# Node_MCU_Schematics_I2C_Pinout_v3_02_202.net
KiCad netlist of a schematic drawn in Altium Designer
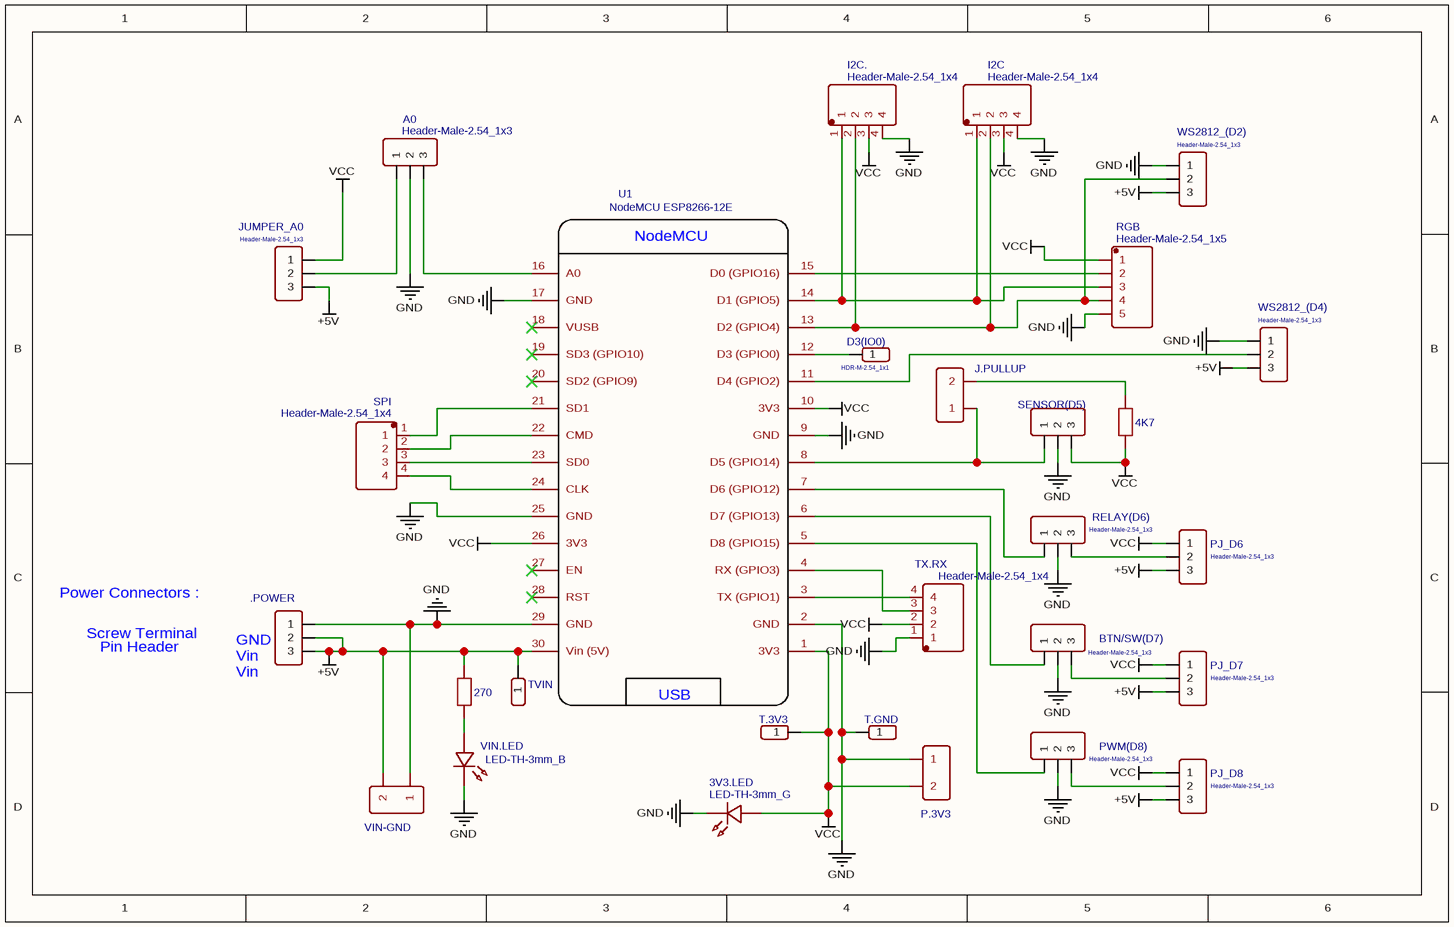
[diagram p0: Node MCU_Schematics I2C Pinout v3.02_2022-01-05.schdoc]

(export (version "E")
  (design (tool "Eeschema 10.0.6"))
  (components
    (comp (ref ".POWER")
      (value "Header-Male-2.54_1x3")
      (fields
        (field (name "BOM_MANUFACTURER PART") "Header2.54mm 1*3P")
        (field (name "BOM_SUPPLIER PART") "C49257")
      )
      (libsource (lib "altium-import") (part "root_2_Header-Male-2.54_1x3_"))
    )
    (comp (ref "3V3.LED")
      (value "LED-TH-3mm_G")
      (fields
        (field (name "BOM_MANUFACTURER PART") "204-10SYGD/S530-E3")
        (field (name "BOM_SUPPLIER PART") "C85161")
        (field (name "CONTRIBUTOR") "LCEDA_Lib")
      )
      (libsource (lib "altium-import") (part "root_2_LED-TH-3mm_G_"))
    )
    (comp (ref "4K7") (value "4k7") (libsource (lib "altium-import") (part "root_1_4k7_")))
    (comp (ref "270") (value "4k7") (libsource (lib "altium-import") (part "root_1_4k7_")))
    (comp (ref "A0")
      (value "Header-Male-2.54_1x3")
      (fields
        (field (name "BOM_MANUFACTURER PART") "Header2.54mm 1*3P")
        (field (name "BOM_SUPPLIER PART") "C49257")
      )
      (libsource (lib "altium-import") (part "root_1_Header-Male-2.54_1x3_"))
    )
    (comp (ref "BTN/SW(D7)")
      (value "Header-Male-2.54_1x3")
      (fields
        (field (name "BOM_MANUFACTURER PART") "Header2.54mm 1*3P")
        (field (name "BOM_SUPPLIER PART") "C49257")
      )
      (libsource (lib "altium-import") (part "root_1_Header-Male-2.54_1x3_"))
    )
    (comp (ref "D3(IO0)")
      (value "HDR-M-2.54_1x1")
      (fields (field (name "BOM_SUPPLIER PART") "C81276") (field (name "CONTRIBUTOR") "LCEDA_Lib"))
      (libsource (lib "altium-import") (part "root_0_HDR-M-2.54_1x1_"))
    )
    (comp (ref "I2C")
      (value "Header-Male-2.54_1x4")
      (fields
        (field (name "BOM_MANUFACTURER PART") "210S-1*4P L=11.6MMGold-plated black")
        (field (name "BOM_SUPPLIER PART") "C124378")
        (field (name "CONTRIBUTOR") "LCSC")
      )
      (libsource (lib "altium-import") (part "root_1_Header-Male-2.54_1x4_"))
    )
    (comp (ref "I2C.")
      (value "Header-Male-2.54_1x4")
      (fields
        (field (name "BOM_MANUFACTURER PART") "210S-1*4P L=11.6MMGold-plated black")
        (field (name "BOM_SUPPLIER PART") "C124378")
        (field (name "CONTRIBUTOR") "LCSC")
      )
      (libsource (lib "altium-import") (part "root_1_Header-Male-2.54_1x4_"))
    )
    (comp (ref "J.PULLUP")
      (value "Header-Male-2.54_1x2")
      (fields (field (name "BOM_MANUFACTURER PART") "826629-2") (field (name "BOM_SUPPLIER PART") "C86471"))
      (libsource (lib "altium-import") (part "root_2_Header-Male-2.54_1x2_"))
    )
    (comp (ref "JUMPER_A0")
      (value "Header-Male-2.54_1x3")
      (fields
        (field (name "BOM_MANUFACTURER PART") "Header2.54mm 1*3P")
        (field (name "BOM_SUPPLIER PART") "C49257")
      )
      (libsource (lib "altium-import") (part "root_0_Header-Male-2.54_1x3_"))
    )
    (comp (ref "P.3V3")
      (value "Header-Male-2.54_1x2")
      (fields (field (name "BOM_MANUFACTURER PART") "826629-2") (field (name "BOM_SUPPLIER PART") "C86471"))
      (libsource (lib "altium-import") (part "root_0_Header-Male-2.54_1x2_"))
    )
    (comp (ref "PJ_D6")
      (value "Header-Male-2.54_1x3")
      (fields
        (field (name "BOM_MANUFACTURER PART") "Header2.54mm 1*3P")
        (field (name "BOM_SUPPLIER PART") "C49257")
      )
      (libsource (lib "") (part "root_0_Header-Male-2.54_1x3__1"))
    )
    (comp (ref "PJ_D7")
      (value "Header-Male-2.54_1x3")
      (fields
        (field (name "BOM_MANUFACTURER PART") "Header2.54mm 1*3P")
        (field (name "BOM_SUPPLIER PART") "C49257")
      )
      (libsource (lib "") (part "root_0_Header-Male-2.54_1x3__1"))
    )
    (comp (ref "PJ_D8")
      (value "Header-Male-2.54_1x3")
      (fields
        (field (name "BOM_MANUFACTURER PART") "Header2.54mm 1*3P")
        (field (name "BOM_SUPPLIER PART") "C49257")
      )
      (libsource (lib "") (part "root_0_Header-Male-2.54_1x3__1"))
    )
    (comp (ref "PWM(D8)")
      (value "Header-Male-2.54_1x3")
      (fields
        (field (name "BOM_MANUFACTURER PART") "Header2.54mm 1*3P")
        (field (name "BOM_SUPPLIER PART") "C49257")
      )
      (libsource (lib "altium-import") (part "root_1_Header-Male-2.54_1x3_"))
    )
    (comp (ref "RELAY(D6)")
      (value "Header-Male-2.54_1x3")
      (fields
        (field (name "BOM_MANUFACTURER PART") "Header2.54mm 1*3P")
        (field (name "BOM_SUPPLIER PART") "C49257")
      )
      (libsource (lib "altium-import") (part "root_1_Header-Male-2.54_1x3_"))
    )
    (comp (ref "RGB")
      (value "Header-Male-2.54_1x5")
      (fields
        (field (name "BOM_MANUFACTURER PART") "210S-1*5P L=11.6MMGold-plated black")
        (field (name "BOM_SUPPLIER PART") "C124379")
        (field (name "CONTRIBUTOR") "LCSC")
      )
      (libsource (lib "altium-import") (part "root_0_Header-Male-2.54_1x5_"))
    )
    (comp (ref "SENSOR(D5)")
      (value "Header-Male-2.54_1x3")
      (fields
        (field (name "BOM_MANUFACTURER PART") "Header2.54mm 1*3P")
        (field (name "BOM_SUPPLIER PART") "C49257")
      )
      (libsource (lib "altium-import") (part "root_1_Header-Male-2.54_1x3_"))
    )
    (comp (ref "SPI")
      (value "Header-Male-2.54_1x4")
      (fields
        (field (name "BOM_MANUFACTURER PART") "210S-1*4P L=11.6MMGold-plated black")
        (field (name "BOM_SUPPLIER PART") "C124378")
        (field (name "CONTRIBUTOR") "LCSC")
      )
      (libsource (lib "altium-import") (part "root_0_Header-Male-2.54_1x4_"))
    )
    (comp (ref "T.3V3")
      (value "Header-Male-2.54_1x1")
      (fields (field (name "BOM_SUPPLIER PART") "C81276"))
      (libsource (lib "altium-import") (part "root_2_Header-Male-2.54_1x1_"))
    )
    (comp (ref "T.GND")
      (value "Header-Male-2.54_1x1")
      (fields (field (name "BOM_SUPPLIER PART") "C81276"))
      (libsource (lib "altium-import") (part "root_0_Header-Male-2.54_1x1_"))
    )
    (comp (ref "TVIN")
      (value "TVin")
      (fields
        (field (name "BOM_MANUFACTURER PART") "Header-Male-2.54_1x1")
        (field (name "BOM_SUPPLIER PART") "C81276")
      )
      (libsource (lib "altium-import") (part "root_3_TVin_"))
    )
    (comp (ref "TX.RX")
      (value "Header-Male-2.54_1x4")
      (fields
        (field (name "BOM_MANUFACTURER PART") "210S-1*4P L=11.6MMGold-plated black")
        (field (name "BOM_SUPPLIER PART") "C124378")
        (field (name "CONTRIBUTOR") "LCSC")
      )
      (libsource (lib "altium-import") (part "root_2_Header-Male-2.54_1x4_"))
    )
    (comp (ref "U1")
      (value "NodeMCU ESP8266-12E")
      (fields
        (field (name "BOM_MANUFACTURER PART") "?")
        (field (name "BOM_SUPPLIER PART") "nodemcu-v2")
        (field (name "CONTRIBUTOR") "irukard")
        (field (name "AUTHOR") "Krzysztof Daszuta")
      )
      (libsource (lib "altium-import") (part "root_2_NodeMCU ESP8266-12E_"))
    )
    (comp (ref "VIN-GND")
      (value "Header-Male-2.54_1x2")
      (fields (field (name "BOM_MANUFACTURER PART") "826629-2") (field (name "BOM_SUPPLIER PART") "C86471"))
      (libsource (lib "altium-import") (part "root_3_Header-Male-2.54_1x2_"))
    )
    (comp (ref "VIN.LED")
      (value "LED-TH-3mm_B")
      (fields
        (field (name "BOM_MANUFACTURER PART") "204-10SUBC/S400-A4")
        (field (name "BOM_SUPPLIER PART") "C86881")
        (field (name "CONTRIBUTOR") "LCEDA_Lib")
      )
      (libsource (lib "altium-import") (part "root_3_LED-TH-3mm_B_"))
    )
    (comp (ref "WS2812_(D2)")
      (value "Header-Male-2.54_1x3")
      (fields
        (field (name "BOM_MANUFACTURER PART") "Header2.54mm 1*3P")
        (field (name "BOM_SUPPLIER PART") "C49257")
      )
      (libsource (lib "") (part "root_0_Header-Male-2.54_1x3__1"))
    )
    (comp (ref "WS2812_(D4)")
      (value "Header-Male-2.54_1x3")
      (fields
        (field (name "BOM_MANUFACTURER PART") "Header2.54mm 1*3P")
        (field (name "BOM_SUPPLIER PART") "C49257")
      )
      (libsource (lib "") (part "root_0_Header-Male-2.54_1x3__1"))
    )
  )
  (nets
    (net (code "1") (name "+5V") (class "Default")
      (node (ref ".POWER") (pin "2") (pinfunction "2_2") (pintype "passive"))
      (node (ref ".POWER") (pin "3") (pinfunction "3_3") (pintype "passive"))
      (node (ref "270") (pin "2") (pinfunction "2_2") (pintype "passive"))
      (node (ref "JUMPER_A0") (pin "3") (pinfunction "3_3") (pintype "passive"))
      (node (ref "PJ_D6") (pin "3") (pinfunction "3_3") (pintype "passive"))
      (node (ref "PJ_D7") (pin "3") (pinfunction "3_3") (pintype "passive"))
      (node (ref "PJ_D8") (pin "3") (pinfunction "3_3") (pintype "passive"))
      (node (ref "TVIN") (pin "1") (pinfunction "1_1") (pintype "passive"))
      (node (ref "U1") (pin "30") (pinfunction "Vin_(5V)_30") (pintype "passive"))
      (node (ref "VIN-GND") (pin "2") (pinfunction "2_2") (pintype "passive"))
      (node (ref "WS2812_(D2)") (pin "3") (pinfunction "3_3") (pintype "passive"))
      (node (ref "WS2812_(D4)") (pin "3") (pinfunction "3_3") (pintype "passive"))
    )
    (net (code "2") (name "GND") (class "Default")
      (node (ref ".POWER") (pin "1") (pinfunction "1_1") (pintype "passive"))
      (node (ref "3V3.LED") (pin "2") (pinfunction "2_2") (pintype "passive"))
      (node (ref "A0") (pin "2") (pinfunction "2_2") (pintype "passive"))
      (node (ref "BTN/SW(D7)") (pin "2") (pinfunction "2_2") (pintype "passive"))
      (node (ref "I2C") (pin "4") (pinfunction "4_4") (pintype "passive"))
      (node (ref "I2C.") (pin "4") (pinfunction "4_4") (pintype "passive"))
      (node (ref "P.3V3") (pin "1") (pinfunction "1_1") (pintype "passive"))
      (node (ref "PWM(D8)") (pin "2") (pinfunction "2_2") (pintype "passive"))
      (node (ref "RELAY(D6)") (pin "2") (pinfunction "2_2") (pintype "passive"))
      (node (ref "RGB") (pin "5") (pinfunction "5_5") (pintype "passive"))
      (node (ref "SENSOR(D5)") (pin "2") (pinfunction "2_2") (pintype "passive"))
      (node (ref "T.GND") (pin "1") (pinfunction "1_1") (pintype "passive"))
      (node (ref "TX.RX") (pin "1") (pinfunction "1_1") (pintype "passive"))
      (node (ref "U1") (pin "17") (pinfunction "GND_17") (pintype "passive"))
      (node (ref "U1") (pin "2") (pinfunction "GND_2") (pintype "passive"))
      (node (ref "U1") (pin "25") (pinfunction "GND_25") (pintype "passive"))
      (node (ref "U1") (pin "29") (pinfunction "GND_29") (pintype "passive"))
      (node (ref "U1") (pin "9") (pinfunction "GND_9") (pintype "passive"))
      (node (ref "VIN-GND") (pin "1") (pinfunction "1_1") (pintype "passive"))
      (node (ref "VIN.LED") (pin "2") (pinfunction "2_2") (pintype "passive"))
      (node (ref "WS2812_(D2)") (pin "1") (pinfunction "1_1") (pintype "passive"))
      (node (ref "WS2812_(D4)") (pin "1") (pinfunction "1_1") (pintype "passive"))
    )
    (net (code "3") (name "Net-(4K7-Pad2)") (class "Default")
      (node (ref "4K7") (pin "2") (pinfunction "2_2") (pintype "passive"))
      (node (ref "J.PULLUP") (pin "2") (pinfunction "2_2") (pintype "passive"))
    )
    (net (code "4") (name "Net-(270-Pad1)") (class "Default")
      (node (ref "270") (pin "1") (pinfunction "1_1") (pintype "passive"))
      (node (ref "VIN.LED") (pin "1") (pinfunction "1_1") (pintype "passive"))
    )
    (net (code "5") (name "Net-(A0-Pad1)") (class "Default")
      (node (ref "A0") (pin "1") (pinfunction "1_1") (pintype "passive"))
      (node (ref "JUMPER_A0") (pin "2") (pinfunction "2_2") (pintype "passive"))
    )
    (net (code "6") (name "Net-(BTN/SW(D7)-Pad3)") (class "Default")
      (node (ref "BTN/SW(D7)") (pin "3") (pinfunction "3_3") (pintype "passive"))
      (node (ref "PJ_D7") (pin "2") (pinfunction "2_2") (pintype "passive"))
    )
    (net (code "7") (name "Net-(PJ_D6-Pad2)") (class "Default")
      (node (ref "PJ_D6") (pin "2") (pinfunction "2_2") (pintype "passive"))
      (node (ref "RELAY(D6)") (pin "3") (pinfunction "3_3") (pintype "passive"))
    )
    (net (code "8") (name "Net-(PJ_D8-Pad2)") (class "Default")
      (node (ref "PJ_D8") (pin "2") (pinfunction "2_2") (pintype "passive"))
      (node (ref "PWM(D8)") (pin "3") (pinfunction "3_3") (pintype "passive"))
    )
    (net (code "9") (name "Net-(U1-A0)") (class "Default")
      (node (ref "A0") (pin "3") (pinfunction "3_3") (pintype "passive"))
      (node (ref "U1") (pin "16") (pinfunction "A0_16") (pintype "passive"))
    )
    (net (code "10") (name "Net-(U1-CLK)") (class "Default")
      (node (ref "SPI") (pin "4") (pinfunction "4_4") (pintype "passive"))
      (node (ref "U1") (pin "24") (pinfunction "CLK_24") (pintype "passive"))
    )
    (net (code "11") (name "Net-(U1-CMD)") (class "Default")
      (node (ref "SPI") (pin "2") (pinfunction "2_2") (pintype "passive"))
      (node (ref "U1") (pin "22") (pinfunction "CMD_22") (pintype "passive"))
    )
    (net (code "12") (name "Net-(U1-D0_(GPIO16))") (class "Default")
      (node (ref "RGB") (pin "2") (pinfunction "2_2") (pintype "passive"))
      (node (ref "U1") (pin "15") (pinfunction "D0_(GPIO16)_15") (pintype "passive"))
    )
    (net (code "13") (name "Net-(U1-D1_(GPIO5))") (class "Default")
      (node (ref "I2C") (pin "1") (pinfunction "1_1") (pintype "passive"))
      (node (ref "I2C.") (pin "1") (pinfunction "1_1") (pintype "passive"))
      (node (ref "RGB") (pin "3") (pinfunction "3_3") (pintype "passive"))
      (node (ref "U1") (pin "14") (pinfunction "D1_(GPIO5)_14") (pintype "passive"))
    )
    (net (code "14") (name "Net-(U1-D2_(GPIO4))") (class "Default")
      (node (ref "I2C") (pin "2") (pinfunction "2_2") (pintype "passive"))
      (node (ref "I2C.") (pin "2") (pinfunction "2_2") (pintype "passive"))
      (node (ref "RGB") (pin "4") (pinfunction "4_4") (pintype "passive"))
      (node (ref "U1") (pin "13") (pinfunction "D2_(GPIO4)_13") (pintype "passive"))
      (node (ref "WS2812_(D2)") (pin "2") (pinfunction "2_2") (pintype "passive"))
    )
    (net (code "15") (name "Net-(U1-D3_(GPIO0))") (class "Default")
      (node (ref "D3(IO0)") (pin "1") (pinfunction "1_1") (pintype "passive"))
      (node (ref "U1") (pin "12") (pinfunction "D3_(GPIO0)_12") (pintype "passive"))
    )
    (net (code "16") (name "Net-(U1-D4_(GPIO2))") (class "Default")
      (node (ref "U1") (pin "11") (pinfunction "D4_(GPIO2)_11") (pintype "passive"))
      (node (ref "WS2812_(D4)") (pin "2") (pinfunction "2_2") (pintype "passive"))
    )
    (net (code "17") (name "Net-(U1-D5_(GPIO14))") (class "Default")
      (node (ref "J.PULLUP") (pin "1") (pinfunction "1_1") (pintype "passive"))
      (node (ref "SENSOR(D5)") (pin "1") (pinfunction "1_1") (pintype "passive"))
      (node (ref "U1") (pin "8") (pinfunction "D5_(GPIO14)_8") (pintype "passive"))
    )
    (net (code "18") (name "Net-(U1-D6_(GPIO12))") (class "Default")
      (node (ref "RELAY(D6)") (pin "1") (pinfunction "1_1") (pintype "passive"))
      (node (ref "U1") (pin "7") (pinfunction "D6_(GPIO12)_7") (pintype "passive"))
    )
    (net (code "19") (name "Net-(U1-D7_(GPIO13))") (class "Default")
      (node (ref "BTN/SW(D7)") (pin "1") (pinfunction "1_1") (pintype "passive"))
      (node (ref "U1") (pin "6") (pinfunction "D7_(GPIO13)_6") (pintype "passive"))
    )
    (net (code "20") (name "Net-(U1-D8_(GPIO15))") (class "Default")
      (node (ref "PWM(D8)") (pin "1") (pinfunction "1_1") (pintype "passive"))
      (node (ref "U1") (pin "5") (pinfunction "D8_(GPIO15)_5") (pintype "passive"))
    )
    (net (code "21") (name "Net-(U1-RX_(GPIO3))") (class "Default")
      (node (ref "TX.RX") (pin "3") (pinfunction "3_3") (pintype "passive"))
      (node (ref "U1") (pin "4") (pinfunction "RX_(GPIO3)_4") (pintype "passive"))
    )
    (net (code "22") (name "Net-(U1-SD0)") (class "Default")
      (node (ref "SPI") (pin "3") (pinfunction "3_3") (pintype "passive"))
      (node (ref "U1") (pin "23") (pinfunction "SD0_23") (pintype "passive"))
    )
    (net (code "23") (name "Net-(U1-SD1)") (class "Default")
      (node (ref "SPI") (pin "1") (pinfunction "1_1") (pintype "passive"))
      (node (ref "U1") (pin "21") (pinfunction "SD1_21") (pintype "passive"))
    )
    (net (code "24") (name "Net-(U1-TX_(GPIO1))") (class "Default")
      (node (ref "TX.RX") (pin "4") (pinfunction "4_4") (pintype "passive"))
      (node (ref "U1") (pin "3") (pinfunction "TX_(GPIO1)_3") (pintype "passive"))
    )
    (net (code "25") (name "VCC") (class "Default")
      (node (ref "3V3.LED") (pin "1") (pinfunction "1_1") (pintype "passive"))
      (node (ref "4K7") (pin "1") (pinfunction "1_1") (pintype "passive"))
      (node (ref "I2C") (pin "3") (pinfunction "3_3") (pintype "passive"))
      (node (ref "I2C.") (pin "3") (pinfunction "3_3") (pintype "passive"))
      (node (ref "JUMPER_A0") (pin "1") (pinfunction "1_1") (pintype "passive"))
      (node (ref "P.3V3") (pin "2") (pinfunction "2_2") (pintype "passive"))
      (node (ref "PJ_D6") (pin "1") (pinfunction "1_1") (pintype "passive"))
      (node (ref "PJ_D7") (pin "1") (pinfunction "1_1") (pintype "passive"))
      (node (ref "PJ_D8") (pin "1") (pinfunction "1_1") (pintype "passive"))
      (node (ref "RGB") (pin "1") (pinfunction "1_1") (pintype "passive"))
      (node (ref "SENSOR(D5)") (pin "3") (pinfunction "3_3") (pintype "passive"))
      (node (ref "T.3V3") (pin "1") (pinfunction "1_1") (pintype "passive"))
      (node (ref "TX.RX") (pin "2") (pinfunction "2_2") (pintype "passive"))
      (node (ref "U1") (pin "1") (pinfunction "3V3_1") (pintype "passive"))
      (node (ref "U1") (pin "10") (pinfunction "3V3_10") (pintype "passive"))
      (node (ref "U1") (pin "26") (pinfunction "3V3_26") (pintype "passive"))
    )
    (net (code "26") (name "unconnected-(U1-EN-Pad27)") (class "Default")
      (node (ref "U1") (pin "27") (pinfunction "EN_27") (pintype "passive+no_connect"))
    )
    (net (code "27") (name "unconnected-(U1-RST-Pad28)") (class "Default")
      (node (ref "U1") (pin "28") (pinfunction "RST_28") (pintype "passive+no_connect"))
    )
    (net (code "28") (name "unconnected-(U1-SD2_(GPIO9)-Pad20)") (class "Default")
      (node (ref "U1") (pin "20") (pinfunction "SD2_(GPIO9)_20") (pintype "passive+no_connect"))
    )
    (net (code "29") (name "unconnected-(U1-SD3_(GPIO10)-Pad19)") (class "Default")
      (node (ref "U1") (pin "19") (pinfunction "SD3_(GPIO10)_19") (pintype "passive+no_connect"))
    )
    (net (code "30") (name "unconnected-(U1-VUSB-Pad18)") (class "Default")
      (node (ref "U1") (pin "18") (pinfunction "VUSB_18") (pintype "passive+no_connect"))
    )
  )
)
